# Sensor_Board.net
KiCad netlist of a schematic drawn in Altium Designer
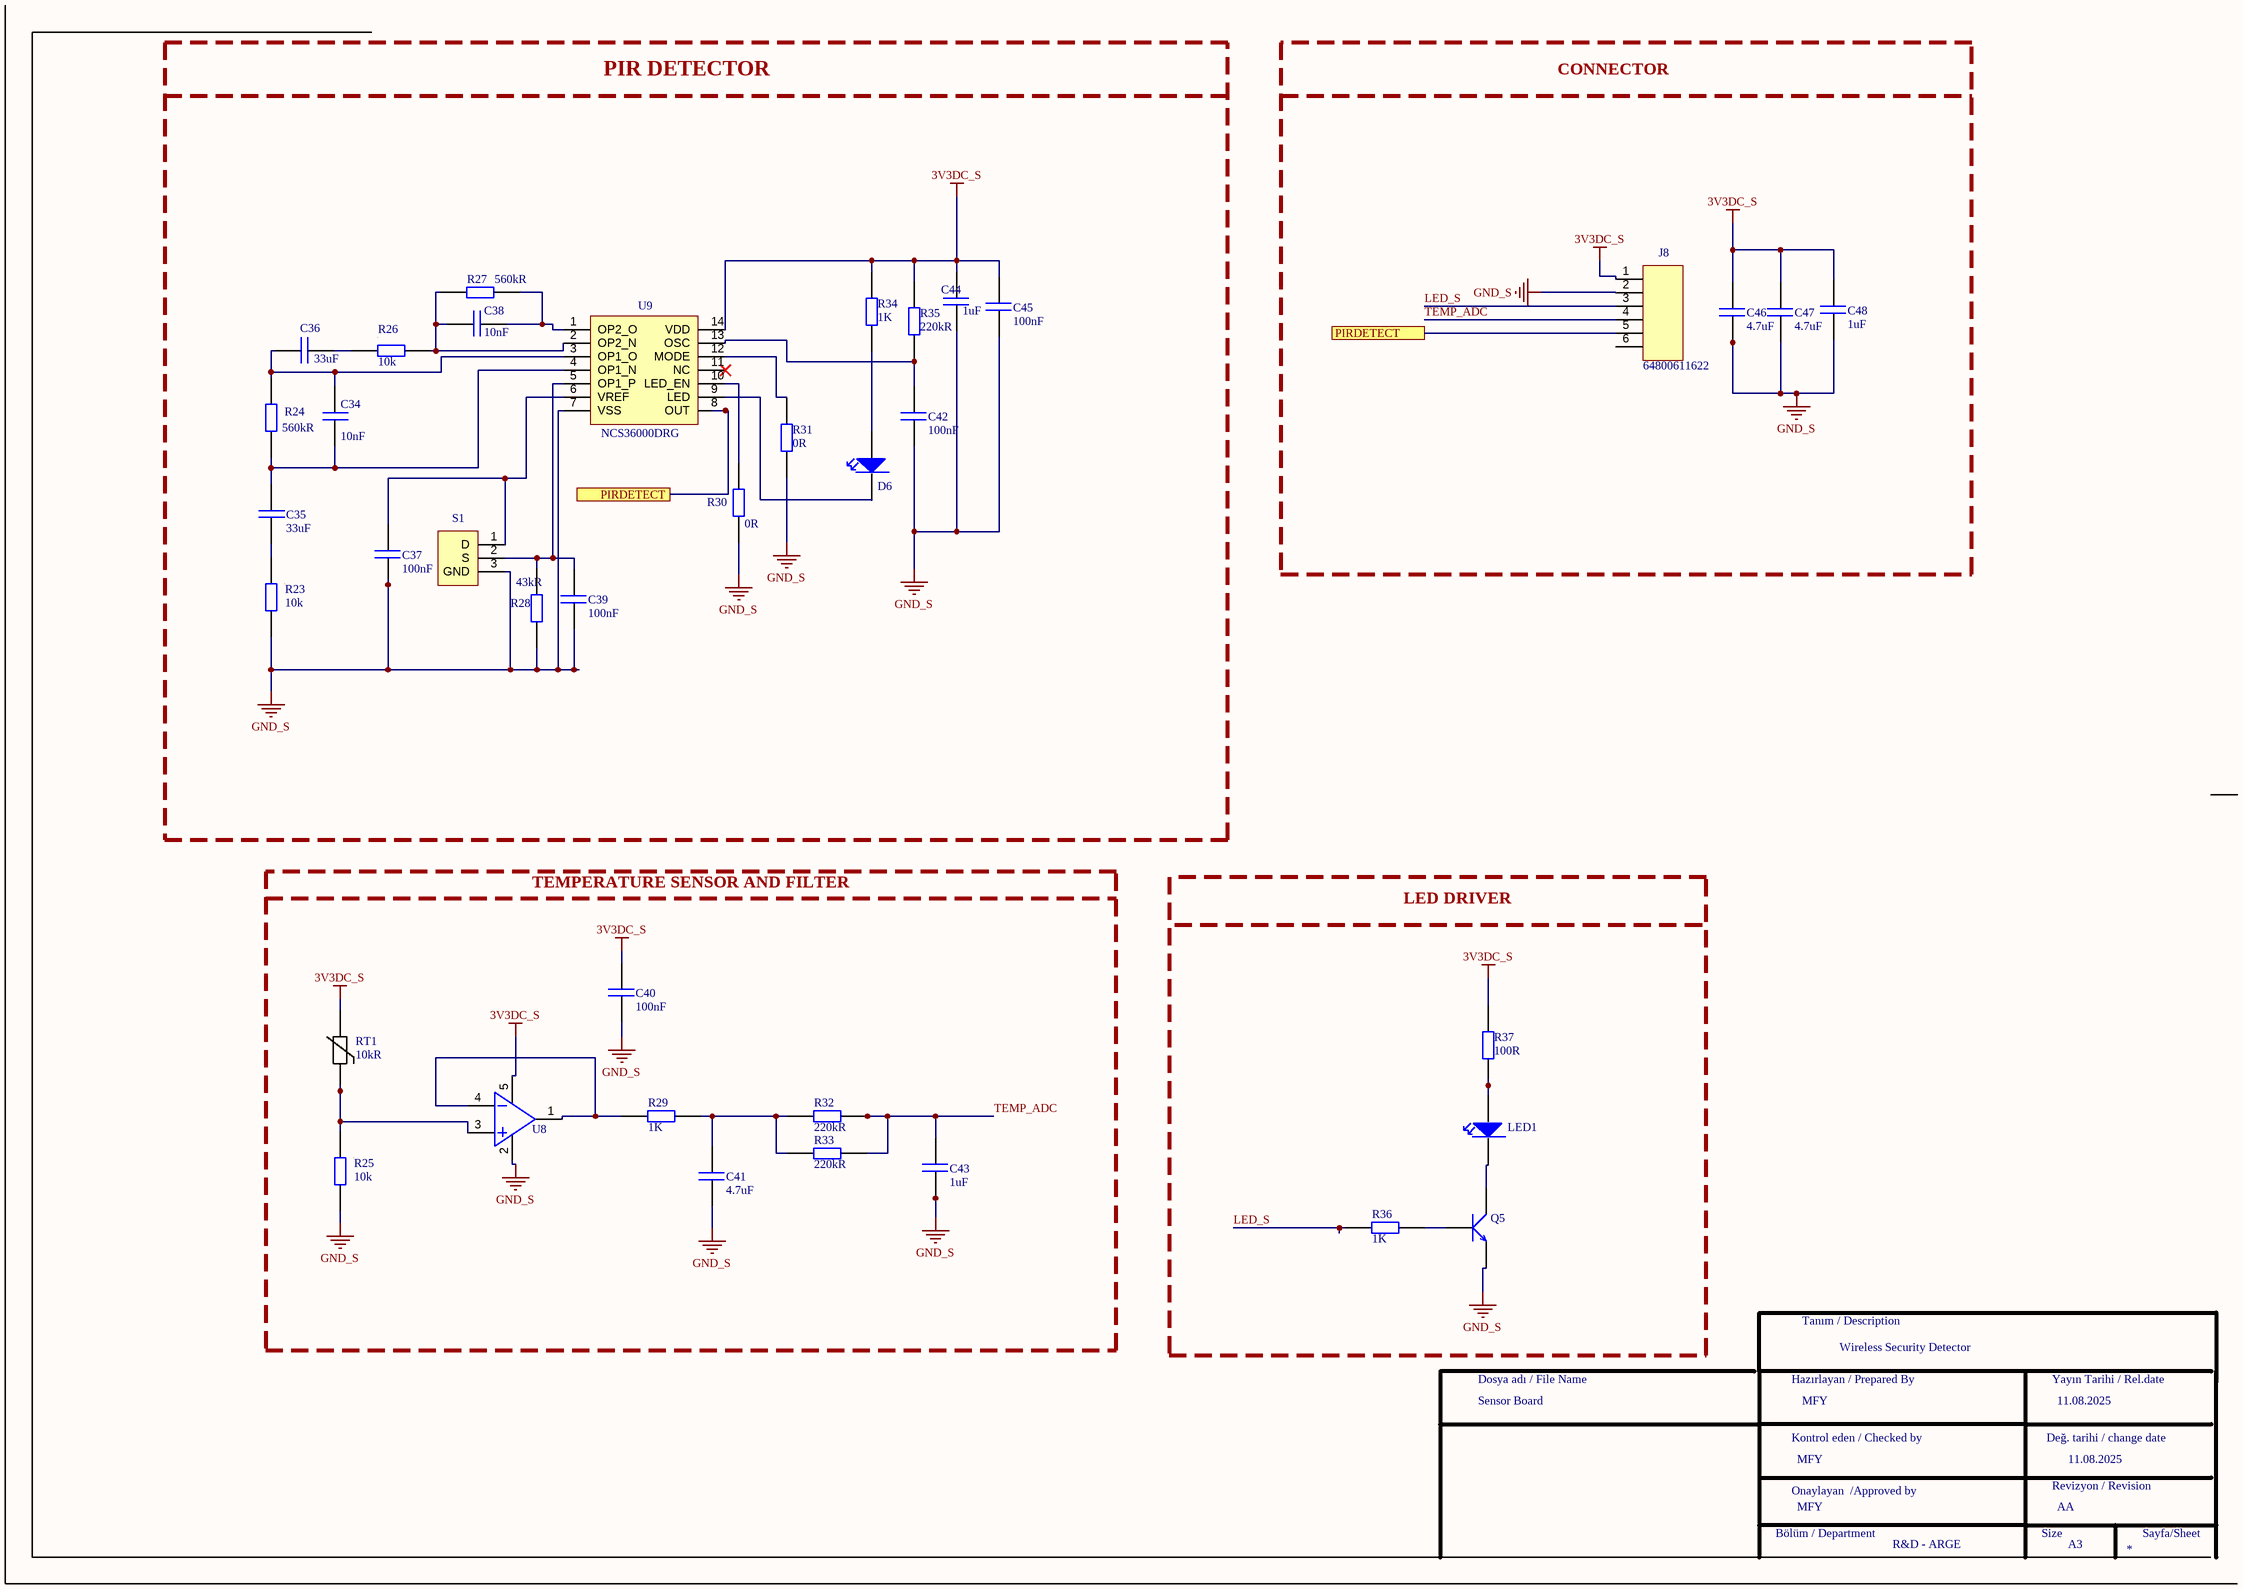
[diagram p0: Sensor Board.SchDoc]

(export (version "E")
  (design (tool "Eeschema 10.0.6"))
  (components
    (comp (ref "C34")
      (value "10nF")
      (footprint "CAP_0603")
      (fields
        (field (name "MANUFACTURER") "Walsin Technologies")
        (field (name "MANUFACTURER PART NUMBER") "0603B103K160CT")
      )
      (libsource (lib "Udemy_Library") (part "CAP CER 10nF 0603"))
    )
    (comp (ref "C35")
      (value "33uF")
      (footprint "CAP_1206")
      (fields
        (field (name "MANUFACTURER") "TDK")
        (field (name "MANUFACTURER PART NUMBER") "C3216X5R1E336M160AC")
      )
      (libsource (lib "Udemy_Library") (part "CAP CER 33uF 1206"))
    )
    (comp (ref "C36")
      (value "33uF")
      (footprint "CAP_1206")
      (fields
        (field (name "MANUFACTURER") "TDK")
        (field (name "MANUFACTURER PART NUMBER") "C3216X5R1E336M160AC")
      )
      (libsource (lib "Udemy_Library") (part "CAP CER 33uF 1206"))
    )
    (comp (ref "C37")
      (value "100nF")
      (footprint "CAP_0603")
      (description "CAP CER %10 100 nF 0603 Kemet")
      (fields
        (field (name "MANUFACTURER") "KEMET")
        (field (name "MANUFACTURER PART NUMBER") "C0603C104K5RACTU")
      )
      (libsource (lib "Udemy_Library") (part "CAP CER 100nF 0603"))
    )
    (comp (ref "C38")
      (value "10nF")
      (footprint "CAP_0603")
      (fields
        (field (name "MANUFACTURER") "Walsin Technologies")
        (field (name "MANUFACTURER PART NUMBER") "0603B103K160CT")
      )
      (libsource (lib "Udemy_Library") (part "CAP CER 10nF 0603"))
    )
    (comp (ref "C39")
      (value "100nF")
      (footprint "CAP_0603")
      (description "CAP CER %10 100 nF 0603 Kemet")
      (fields
        (field (name "MANUFACTURER") "KEMET")
        (field (name "MANUFACTURER PART NUMBER") "C0603C104K5RACTU")
      )
      (libsource (lib "Udemy_Library") (part "CAP CER 100nF 0603"))
    )
    (comp (ref "C40")
      (value "100nF")
      (footprint "CAP_0603")
      (description "CAP CER %10 100 nF 0603 Kemet")
      (fields
        (field (name "MANUFACTURER") "KEMET")
        (field (name "MANUFACTURER PART NUMBER") "C0603C104K5RACTU")
      )
      (libsource (lib "Udemy_Library") (part "CAP CER 100nF 0603"))
    )
    (comp (ref "C41")
      (value "4.7uF")
      (footprint "CAP_0805")
      (fields
        (field (name "MANUFACTURER") "Samsung")
        (field (name "MANUFACTURER PART NUMBER") "CL21A475KAQNNNE")
      )
      (libsource (lib "Udemy_Library") (part "CAP CER 4.7uF 0805"))
    )
    (comp (ref "C42")
      (value "100nF")
      (footprint "CAP_0603")
      (description "CAP CER %10 100 nF 0603 Kemet")
      (fields
        (field (name "MANUFACTURER") "KEMET")
        (field (name "MANUFACTURER PART NUMBER") "C0603C104K5RACTU")
      )
      (libsource (lib "Udemy_Library") (part "CAP CER 100nF 0603"))
    )
    (comp (ref "C43")
      (value "1uF")
      (footprint "CAP_0805")
      (fields
        (field (name "MANUFACTURER") "Samsung")
        (field (name "MANUFACTURER PART NUMBER") "CL21B105KBFNNNE")
      )
      (libsource (lib "Udemy_Library") (part "CAP CER 1uF 0805"))
    )
    (comp (ref "C44")
      (value "1uF")
      (footprint "CAP_0805")
      (fields
        (field (name "MANUFACTURER") "Samsung")
        (field (name "MANUFACTURER PART NUMBER") "CL21B105KBFNNNE")
      )
      (libsource (lib "Udemy_Library") (part "CAP CER 1uF 0805"))
    )
    (comp (ref "C45")
      (value "100nF")
      (footprint "CAP_0603")
      (description "CAP CER %10 100 nF 0603 Kemet")
      (fields
        (field (name "MANUFACTURER") "KEMET")
        (field (name "MANUFACTURER PART NUMBER") "C0603C104K5RACTU")
      )
      (libsource (lib "Udemy_Library") (part "CAP CER 100nF 0603"))
    )
    (comp (ref "C46")
      (value "4.7uF")
      (footprint "CAP_0805")
      (fields
        (field (name "MANUFACTURER") "Samsung")
        (field (name "MANUFACTURER PART NUMBER") "CL21A475KAQNNNE")
      )
      (libsource (lib "Udemy_Library") (part "CAP CER 4.7uF 0805"))
    )
    (comp (ref "C47")
      (value "4.7uF")
      (footprint "CAP_0805")
      (fields
        (field (name "MANUFACTURER") "Samsung")
        (field (name "MANUFACTURER PART NUMBER") "CL21A475KAQNNNE")
      )
      (libsource (lib "Udemy_Library") (part "CAP CER 4.7uF 0805"))
    )
    (comp (ref "C48")
      (value "1uF")
      (footprint "CAP_0805")
      (fields
        (field (name "MANUFACTURER") "Samsung")
        (field (name "MANUFACTURER PART NUMBER") "CL21B105KBFNNNE")
      )
      (libsource (lib "Udemy_Library") (part "CAP CER 1uF 0805"))
    )
    (comp (ref "D6")
      (value "LTST-C171GKT")
      (footprint "LED_GREEN_0805")
      (description "Single Color LED, Green, Water Clear, 1.4mm")
      (fields (field (name "MANUFACTURER") "Vishay Lite-On"))
      (libsource (lib "Udemy_Library") (part "LED_GREEN_0805"))
    )
    (comp (ref "J8")
      (value "64800611622")
      (footprint "64800611622_WÜRTH_CONN")
      (description "WR-WTB Wire-to-Board Connectors 1.50 mm(ANA KARTTAN SENSOR KARTA)")
      (fields (field (name "MANUFACTURER") "Wurth Electronics"))
      (libsource (lib "Udemy_Library") (part "64800611622_CONN_6PIN"))
    )
    (comp (ref "LED1")
      (value "LH R974-LP-1")
      (footprint "LED_RED_0805")
      (description "Red 645nm LED Indication - Discrete 1.8V 0805 (2012 Metric)")
      (libsource (lib "Udemy_Library") (part "LED RED 0805"))
    )
    (comp (ref "Q5")
      (value "MMBT3904-7-F")
      (footprint "SOT23-F")
      (fields (field (name "MANUFACTURER") "Diodes Zetex") (field (name "DESIGNED BY") "MFY"))
      (libsource (lib "Udemy_Library") (part "MMBT3904-7-F"))
    )
    (comp (ref "R23")
      (value "10k")
      (footprint "RES_0603")
      (description "RES 10K %1 OHM 0603 SMD")
      (fields
        (field (name "MANUFACTURER") "Yageo Group")
        (field (name "MANUFACTURER PART NUMBER") "RC0603FR-0710KL")
        (field (name "DESIGNED BY") "MFY")
      )
      (libsource (lib "") (part "RES 10K OHM 0603_1"))
    )
    (comp (ref "R24")
      (value "560kR")
      (footprint "RES_0603")
      (description "560K %5 RES , Surface Mount, 0603")
      (fields
        (field (name "MANUFACTURER") "Yageo")
        (field (name "MANUFACTURER PART NUMBER") "RC0603JR-07560KL")
      )
      (libsource (lib "Udemy_Library") (part "RES 560K OHM 0603"))
    )
    (comp (ref "R25")
      (value "10k")
      (footprint "RES_0603")
      (description "RES 10K %1 OHM 0603 SMD")
      (fields
        (field (name "MANUFACTURER") "Yageo Group")
        (field (name "MANUFACTURER PART NUMBER") "RC0603FR-0710KL")
        (field (name "DESIGNED BY") "MFY")
      )
      (libsource (lib "") (part "RES 10K OHM 0603_1"))
    )
    (comp (ref "R26")
      (value "10k")
      (footprint "RES_0603")
      (description "RES 10K %1 OHM 0603 SMD")
      (fields
        (field (name "MANUFACTURER") "Yageo Group")
        (field (name "MANUFACTURER PART NUMBER") "RC0603FR-0710KL")
        (field (name "DESIGNED BY") "MFY")
      )
      (libsource (lib "Udemy_Library") (part "RES 10K OHM 0603"))
    )
    (comp (ref "R27")
      (value "560kR")
      (footprint "RES_0603")
      (description "560K %5 RES , Surface Mount, 0603")
      (fields
        (field (name "MANUFACTURER") "Yageo")
        (field (name "MANUFACTURER PART NUMBER") "RC0603JR-07560KL")
      )
      (libsource (lib "") (part "RES 560K OHM 0603_1"))
    )
    (comp (ref "R28")
      (value "43kR")
      (footprint "RES_0603")
      (description "0.1W, 43Kohm, 75V, 5% +/-Tol, 100ppm/Cel, Surface Mount, 0603")
      (fields
        (field (name "MANUFACTURER") "Yageo")
        (field (name "MANUFACTURER PART NUMBER") "RC0603JR-0743KL")
      )
      (libsource (lib "Udemy_Library") (part "RES 43K OHM 0603"))
    )
    (comp (ref "R29")
      (value "1K")
      (footprint "RES_0603")
      (fields (field (name "Comment") "RES 1K OHM 0603"))
      (libsource (lib "Udemy_Library") (part "RES 1K OHM 0603"))
    )
    (comp (ref "R30")
      (value "0R")
      (footprint "RES_0603")
      (description "Metal Glaze/thick Film, 0.1W, 0ohm, Surface Mount, 0603")
      (fields
        (field (name "MANUFACTURER") "Yageo")
        (field (name "MANUFACTURER PART NUMBER") "RC0603JR-070RL")
      )
      (libsource (lib "Udemy_Library") (part "RES 0 OHM 0603"))
    )
    (comp (ref "R31")
      (value "0R")
      (footprint "RES_0603")
      (description "Metal Glaze/thick Film, 0.1W, 0ohm, Surface Mount, 0603")
      (fields
        (field (name "MANUFACTURER") "Yageo")
        (field (name "MANUFACTURER PART NUMBER") "RC0603JR-070RL")
      )
      (libsource (lib "Udemy_Library") (part "RES 0 OHM 0603"))
    )
    (comp (ref "R32")
      (value "220kR")
      (footprint "RES_0603")
      (description "0.1W, 220000ohm, 75V, 5% +/-Tol, 100ppm/Cel, Surface Mount, 0603")
      (fields
        (field (name "MANUFACTURER") "Yageo")
        (field (name "MANUFACTURER PART NUMBER") "RC0603JR-07220KL")
      )
      (libsource (lib "Udemy_Library") (part "RES 220K OHM 0603"))
    )
    (comp (ref "R33")
      (value "220kR")
      (footprint "RES_0603")
      (description "0.1W, 220000ohm, 75V, 5% +/-Tol, 100ppm/Cel, Surface Mount, 0603")
      (fields
        (field (name "MANUFACTURER") "Yageo")
        (field (name "MANUFACTURER PART NUMBER") "RC0603JR-07220KL")
      )
      (libsource (lib "Udemy_Library") (part "RES 220K OHM 0603"))
    )
    (comp (ref "R34")
      (value "1K")
      (footprint "RES_0603")
      (fields (field (name "Comment") "RES 1K OHM 0603"))
      (libsource (lib "") (part "RES 1K OHM 0603_1"))
    )
    (comp (ref "R35")
      (value "220kR")
      (footprint "RES_0603")
      (description "0.1W, 220000ohm, 75V, 5% +/-Tol, 100ppm/Cel, Surface Mount, 0603")
      (fields
        (field (name "MANUFACTURER") "Yageo")
        (field (name "MANUFACTURER PART NUMBER") "RC0603JR-07220KL")
      )
      (libsource (lib "") (part "RES 220K OHM 0603_1"))
    )
    (comp (ref "R36")
      (value "1K")
      (footprint "RES_0603")
      (fields (field (name "Comment") "RES 1K OHM 0603"))
      (libsource (lib "Udemy_Library") (part "RES 1K OHM 0603"))
    )
    (comp (ref "R37")
      (value "100R")
      (footprint "RES_0603")
      (fields (field (name "Comment") "RES 100 OHM 0603"))
      (libsource (lib "Udemy_Library") (part "RES 100 OHM 0603"))
    )
    (comp (ref "RT1")
      (value "10kR")
      (footprint "RES_1206")
      (description "Thermistor PTC 10K Ohm 1% 2-Pin 1206 Surface Mount")
      (fields
        (field (name "MANUFACTURER") "Vishay Dale")
        (field (name "MANUFACTURER PART NUMBER") "TFPT1206L1002FM")
        (field (name "DESIGNED BY") "MFY")
      )
      (libsource (lib "Udemy_Library") (part "TFPT1206L1002FM"))
    )
    (comp (ref "S1")
      (value "LHI 878/3902")
      (footprint "LHI 878/3902")
      (description "Sensor PIR (Passive Infrared) TO-205AA, TO-5-3 Metal Can")
      (fields
        (field (name "MANUFACTURER") "Excelitas")
        (field (name "MANUFACTURER PART NUMBER") "LHI878/3902")
        (field (name "DESIGNED BY") "MFY")
      )
      (libsource (lib "Udemy_Library") (part "LHI 878/3902"))
    )
    (comp (ref "U8")
      (value "OPA314AIDBVR")
      (footprint "SOT23-5")
      (description "OPAMP OPA 314")
      (fields (field (name "MANUFACTURER") "Texas Instruments") (field (name "POWER") "No"))
      (libsource (lib "Udemy_Library") (part "OPA 314"))
    )
    (comp (ref "U9")
      (value "NCS36000DRG")
      (footprint "SOIC14")
      (description "PIR CONTROLLER Analog Circuit, 1 Func, CMOS, PDSO14")
      (fields (field (name "MANUFACTURER") "onsemi"))
      (libsource (lib "Udemy_Library") (part "NCS36000"))
    )
  )
  (nets
    (net (code "1") (name "/LED_S") (class "Default")
      (node (ref "J8") (pin "3") (pinfunction "RX_3") (pintype "power_in"))
      (node (ref "R36") (pin "1") (pinfunction "1_1") (pintype "passive"))
    )
    (net (code "2") (name "/PIRDETECT") (class "Default")
      (node (ref "J8") (pin "5") (pinfunction "GND_5") (pintype "power_in"))
      (node (ref "U9") (pin "8") (pinfunction "OUT_8") (pintype "passive"))
    )
    (net (code "3") (name "/TEMP_ADC") (class "Default")
      (node (ref "C43") (pin "2") (pinfunction "2_2") (pintype "passive"))
      (node (ref "J8") (pin "4") (pinfunction "NC_4") (pintype "power_in"))
      (node (ref "R32") (pin "2") (pinfunction "2_2") (pintype "passive"))
      (node (ref "R33") (pin "2") (pinfunction "2_2") (pintype "passive"))
    )
    (net (code "4") (name "3V3DC_S") (class "Default")
      (node (ref "C40") (pin "2") (pinfunction "2_2") (pintype "passive"))
      (node (ref "C44") (pin "2") (pinfunction "2_2") (pintype "passive"))
      (node (ref "C45") (pin "2") (pinfunction "2_2") (pintype "passive"))
      (node (ref "C46") (pin "2") (pinfunction "2_2") (pintype "passive"))
      (node (ref "C47") (pin "2") (pinfunction "2_2") (pintype "passive"))
      (node (ref "C48") (pin "2") (pinfunction "2_2") (pintype "passive"))
      (node (ref "J8") (pin "1") (pinfunction "VCC_1") (pintype "power_in"))
      (node (ref "R34") (pin "2") (pinfunction "2_2") (pintype "passive"))
      (node (ref "R35") (pin "2") (pinfunction "2_2") (pintype "passive"))
      (node (ref "R37") (pin "1") (pinfunction "1_1") (pintype "passive"))
      (node (ref "RT1") (pin "2") (pinfunction "2_2") (pintype "passive"))
      (node (ref "U8") (pin "5") (pinfunction "5_5") (pintype "passive"))
      (node (ref "U9") (pin "14") (pinfunction "VDD_14") (pintype "passive"))
    )
    (net (code "5") (name "GND_S") (class "Default")
      (node (ref "C37") (pin "1") (pinfunction "1_1") (pintype "passive"))
      (node (ref "C39") (pin "1") (pinfunction "1_1") (pintype "passive"))
      (node (ref "C40") (pin "1") (pinfunction "1_1") (pintype "passive"))
      (node (ref "C41") (pin "1") (pinfunction "1_1") (pintype "passive"))
      (node (ref "C42") (pin "1") (pinfunction "1_1") (pintype "passive"))
      (node (ref "C43") (pin "1") (pinfunction "1_1") (pintype "passive"))
      (node (ref "C44") (pin "1") (pinfunction "1_1") (pintype "passive"))
      (node (ref "C45") (pin "1") (pinfunction "1_1") (pintype "passive"))
      (node (ref "C46") (pin "1") (pinfunction "1_1") (pintype "passive"))
      (node (ref "C47") (pin "1") (pinfunction "1_1") (pintype "passive"))
      (node (ref "C48") (pin "1") (pinfunction "1_1") (pintype "passive"))
      (node (ref "J8") (pin "2") (pinfunction "RX_2") (pintype "power_in"))
      (node (ref "Q5") (pin "2") (pinfunction "E_2") (pintype "passive"))
      (node (ref "R23") (pin "2") (pinfunction "2_2") (pintype "passive"))
      (node (ref "R25") (pin "2") (pinfunction "2_2") (pintype "passive"))
      (node (ref "R28") (pin "1") (pinfunction "1_1") (pintype "passive"))
      (node (ref "R30") (pin "1") (pinfunction "1_1") (pintype "passive"))
      (node (ref "R31") (pin "1") (pinfunction "1_1") (pintype "passive"))
      (node (ref "S1") (pin "3") (pinfunction "GND_3") (pintype "passive"))
      (node (ref "U8") (pin "2") (pinfunction "2_2") (pintype "passive"))
      (node (ref "U9") (pin "7") (pinfunction "VSS_7") (pintype "passive"))
    )
    (net (code "6") (name "Net-(C35-Pad2)") (class "Default")
      (node (ref "C35") (pin "2") (pinfunction "2_2") (pintype "passive"))
      (node (ref "R23") (pin "1") (pinfunction "1_1") (pintype "passive"))
    )
    (net (code "7") (name "Net-(C36-Pad2)") (class "Default")
      (node (ref "C36") (pin "2") (pinfunction "2_2") (pintype "passive"))
      (node (ref "R26") (pin "1") (pinfunction "1_1") (pintype "passive"))
    )
    (net (code "8") (name "Net-(C41-Pad2)") (class "Default")
      (node (ref "C41") (pin "2") (pinfunction "2_2") (pintype "passive"))
      (node (ref "R29") (pin "2") (pinfunction "2_2") (pintype "passive"))
      (node (ref "R32") (pin "1") (pinfunction "1_1") (pintype "passive"))
      (node (ref "R33") (pin "1") (pinfunction "1_1") (pintype "passive"))
    )
    (net (code "9") (name "Net-(D6-Pad2)") (class "Default")
      (node (ref "D6") (pin "2") (pinfunction "2_2") (pintype "passive"))
      (node (ref "R34") (pin "1") (pinfunction "1_1") (pintype "passive"))
    )
    (net (code "10") (name "Net-(LED1-Pad2)") (class "Default")
      (node (ref "LED1") (pin "2") (pinfunction "2_2") (pintype "passive"))
      (node (ref "R37") (pin "2") (pinfunction "2_2") (pintype "passive"))
    )
    (net (code "11") (name "Net-(Q5-B)") (class "Default")
      (node (ref "Q5") (pin "1") (pinfunction "B_1") (pintype "passive"))
      (node (ref "R36") (pin "2") (pinfunction "2_2") (pintype "passive"))
    )
    (net (code "12") (name "Net-(Q5-C)") (class "Default")
      (node (ref "LED1") (pin "1") (pinfunction "1_1") (pintype "passive"))
      (node (ref "Q5") (pin "3") (pinfunction "C_3") (pintype "passive"))
    )
    (net (code "13") (name "Net-(R25-Pad1)") (class "Default")
      (node (ref "R25") (pin "1") (pinfunction "1_1") (pintype "passive"))
      (node (ref "RT1") (pin "1") (pinfunction "1_1") (pintype "passive"))
      (node (ref "U8") (pin "3") (pinfunction "3_3") (pintype "passive"))
    )
    (net (code "14") (name "Net-(R29-Pad1)") (class "Default")
      (node (ref "R29") (pin "1") (pinfunction "1_1") (pintype "passive"))
      (node (ref "U8") (pin "1") (pinfunction "1_1") (pintype "passive"))
      (node (ref "U8") (pin "4") (pinfunction "4_4") (pintype "passive"))
    )
    (net (code "15") (name "Net-(S1-D)") (class "Default")
      (node (ref "C37") (pin "2") (pinfunction "2_2") (pintype "passive"))
      (node (ref "S1") (pin "1") (pinfunction "D_1") (pintype "passive"))
      (node (ref "U9") (pin "6") (pinfunction "VREF_6") (pintype "passive"))
    )
    (net (code "16") (name "Net-(S1-S)") (class "Default")
      (node (ref "C39") (pin "2") (pinfunction "2_2") (pintype "passive"))
      (node (ref "R28") (pin "2") (pinfunction "2_2") (pintype "passive"))
      (node (ref "S1") (pin "2") (pinfunction "S_2") (pintype "passive"))
      (node (ref "U9") (pin "5") (pinfunction "OP1_P_5") (pintype "passive"))
    )
    (net (code "17") (name "Net-(U9-LED)") (class "Default")
      (node (ref "D6") (pin "1") (pinfunction "1_1") (pintype "passive"))
      (node (ref "U9") (pin "9") (pinfunction "LED_9") (pintype "passive"))
    )
    (net (code "18") (name "Net-(U9-LED_EN)") (class "Default")
      (node (ref "R30") (pin "2") (pinfunction "2_2") (pintype "passive"))
      (node (ref "U9") (pin "10") (pinfunction "LED_EN_10") (pintype "passive"))
    )
    (net (code "19") (name "Net-(U9-MODE)") (class "Default")
      (node (ref "R31") (pin "2") (pinfunction "2_2") (pintype "passive"))
      (node (ref "U9") (pin "12") (pinfunction "MODE_12") (pintype "passive"))
    )
    (net (code "20") (name "Net-(U9-OP1_N)") (class "Default")
      (node (ref "C34") (pin "2") (pinfunction "2_2") (pintype "passive"))
      (node (ref "C35") (pin "1") (pinfunction "1_1") (pintype "passive"))
      (node (ref "R24") (pin "2") (pinfunction "2_2") (pintype "passive"))
      (node (ref "U9") (pin "4") (pinfunction "OP1_N_4") (pintype "passive"))
    )
    (net (code "21") (name "Net-(U9-OP1_O)") (class "Default")
      (node (ref "C34") (pin "1") (pinfunction "1_1") (pintype "passive"))
      (node (ref "C36") (pin "1") (pinfunction "1_1") (pintype "passive"))
      (node (ref "R24") (pin "1") (pinfunction "1_1") (pintype "passive"))
      (node (ref "U9") (pin "3") (pinfunction "OP1_O_3") (pintype "passive"))
    )
    (net (code "22") (name "Net-(U9-OP2_N)") (class "Default")
      (node (ref "C38") (pin "1") (pinfunction "1_1") (pintype "passive"))
      (node (ref "R26") (pin "2") (pinfunction "2_2") (pintype "passive"))
      (node (ref "R27") (pin "1") (pinfunction "1_1") (pintype "passive"))
      (node (ref "U9") (pin "2") (pinfunction "OP2_N_2") (pintype "passive"))
    )
    (net (code "23") (name "Net-(U9-OP2_O)") (class "Default")
      (node (ref "C38") (pin "2") (pinfunction "2_2") (pintype "passive"))
      (node (ref "R27") (pin "2") (pinfunction "2_2") (pintype "passive"))
      (node (ref "U9") (pin "1") (pinfunction "OP2_O_1") (pintype "passive"))
    )
    (net (code "24") (name "Net-(U9-OSC)") (class "Default")
      (node (ref "C42") (pin "2") (pinfunction "2_2") (pintype "passive"))
      (node (ref "R35") (pin "1") (pinfunction "1_1") (pintype "passive"))
      (node (ref "U9") (pin "13") (pinfunction "OSC_13") (pintype "passive"))
    )
    (net (code "25") (name "unconnected-(J8-GND-Pad6)") (class "Default")
      (node (ref "J8") (pin "6") (pinfunction "GND_6") (pintype "power_in"))
    )
    (net (code "26") (name "unconnected-(U9-NC-Pad11)") (class "Default")
      (node (ref "U9") (pin "11") (pinfunction "NC_11") (pintype "passive+no_connect"))
    )
  )
)
